# test_sch.net
KiCad netlist of a schematic drawn in Altium Designer
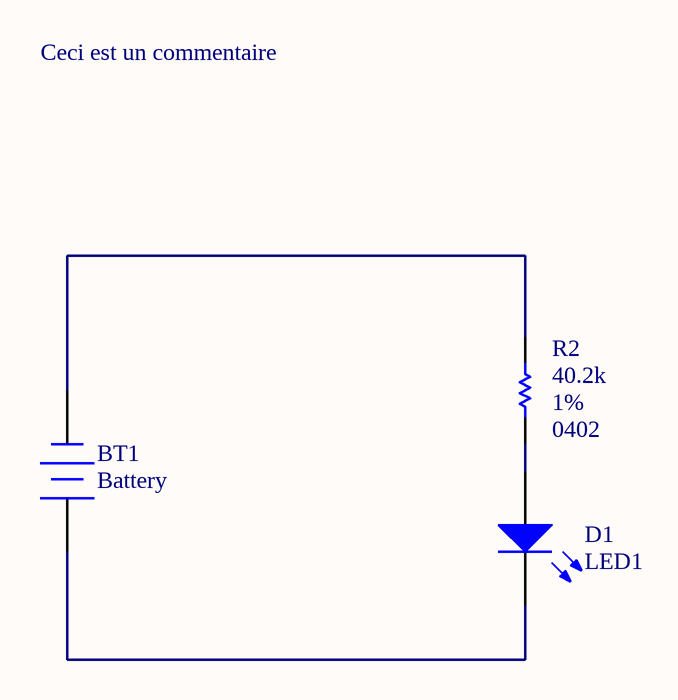
[diagram p0: test_sch.SchDoc]

(export (version "E")
  (design (tool "Eeschema 10.0.6"))
  (components
    (comp (ref "BT1")
      (value "Battery")
      (footprint "BAT-2")
      (description "Multicell Battery")
      (fields (field (name "PUBLISHER") "Altium Limited"))
      (libsource (lib "Miscellaneous Devices") (part "Battery"))
    )
    (comp (ref "D1")
      (value "LED1")
      (footprint "LED-1")
      (description "Typical RED GaAs LED")
      (fields (field (name "PUBLISHER") "Altium Limited"))
      (libsource (lib "Miscellaneous Devices") (part "LED1"))
    )
    (comp (ref "R2")
      (value "40.2k")
      (footprint "RESC0402(1005)_L")
      (description "0402 (1005 Metric) Chip Resistor")
      (fields
        (field (name "CASE-EIA") "0402")
        (field (name "TOLERANCE") "1%")
        (field (name "Comment") "RES0402")
      )
      (libsource (lib "Altium Content Vault") (part "RES_3"))
    )
  )
  (nets
    (net (code "1") (name "Net-(BT1-+)") (class "Default")
      (node (ref "BT1") (pin "1") (pinfunction "+_1") (pintype "passive"))
      (node (ref "D1") (pin "2") (pinfunction "K_2") (pintype "passive"))
    )
    (net (code "2") (name "Net-(BT1--)") (class "Default")
      (node (ref "BT1") (pin "2") (pinfunction "-_2") (pintype "passive"))
      (node (ref "R2") (pin "2") (pinfunction "2_2") (pintype "passive"))
    )
    (net (code "3") (name "Net-(D1-A)") (class "Default")
      (node (ref "D1") (pin "1") (pinfunction "A_1") (pintype "passive"))
      (node (ref "R2") (pin "1") (pinfunction "1_1") (pintype "passive"))
    )
  )
)
